# MCU.net
KiCad netlist of a schematic drawn in Altium Designer
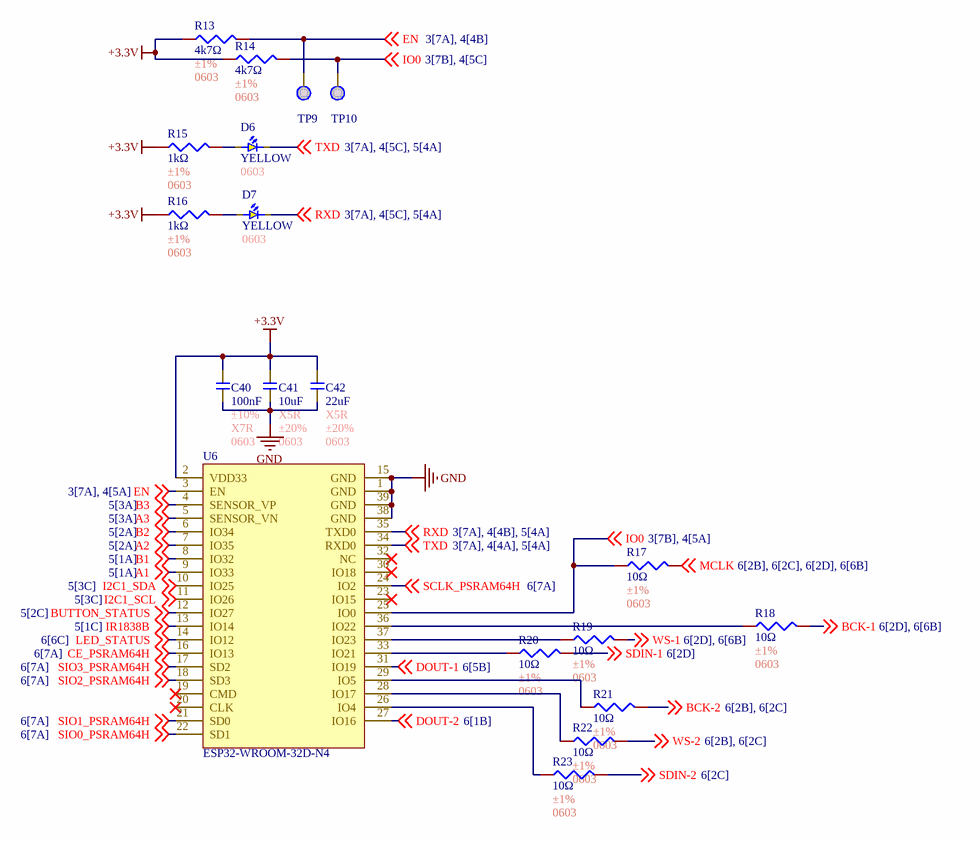
[diagram p0: MCU.SchDoc]

(export (version "E")
  (design (tool "Eeschema 10.0.6"))
  (components
    (comp (ref "C40")
      (value "100nF")
      (footprint "C0603")
      (description "50V 100nF X7R ±10% 0603 Multilayer Ceramic Capacitors MLCC - SMD/SMT ROHS")
      (fields
        (field (name "MANUFACTURER") "YAGEO")
        (field (name "MFR. PART #") "CC0603KRX7R9BB104")
        (field (name "TOLERANCE") "±10%")
        (field (name "TEMPERATURE COEFFICIENT") "X7R")
        (field (name "PACKAGE") "0603")
      )
      (libsource (lib "DSP_VERSION_1.0") (part "C0603_100nF_±10%_X7R"))
    )
    (comp (ref "C41")
      (value "10uF")
      (footprint "C0603")
      (description "25V 10uF X5R ±20% 0603 Multilayer Ceramic Capacitors MLCC - SMD/SMT ROHS")
      (fields
        (field (name "MANUFACTURER") "YAGEO")
        (field (name "MFR. PART #") "CC0603MRX5R8BB106")
        (field (name "TEMPERATURE COEFFICIENT") "X5R")
        (field (name "TOLERANCE") "±20%")
        (field (name "PACKAGE") "0603")
      )
      (libsource (lib "DSP_VERSION_1.0") (part "C0603_10uF_±10%_X7R"))
    )
    (comp (ref "C42")
      (value "22uF")
      (footprint "C0603")
      (description "6.3V 22uF X5R ±20% 0603 Multilayer Ceramic Capacitors MLCC - SMD/SMT ROHS")
      (fields
        (field (name "MANUFACTURER") "YAGEO")
        (field (name "MFR. PART #") "CC0603MRX5R5BB226")
        (field (name "TEMPERATURE COEFFICIENT") "X5R")
        (field (name "TOLERANCE") "±20%")
        (field (name "PACKAGE") "0603")
      )
      (libsource (lib "DSP_VERSION_1.0") (part "C0603_22uF_±20%_X5R"))
    )
    (comp (ref "D6")
      (value "YELLOW")
      (footprint "LED0603")
      (description "25mcd~40mcd Water Clear -40℃~+85℃ 624nm Red 120° 60mW 0402 LED Indication - Discrete ROHS")
      (fields
        (field (name "MANUFACTURER") "XINGLIGHT")
        (field (name "MFR. PART #") "XL-1005UGC")
        (field (name "PACKAGE") "0603")
      )
      (libsource (lib "LED") (part "D0603_YELLOW"))
    )
    (comp (ref "D7")
      (value "YELLOW")
      (footprint "LED0603")
      (description "25mcd~40mcd Water Clear -40℃~+85℃ 624nm Red 120° 60mW 0402 LED Indication - Discrete ROHS")
      (fields
        (field (name "MANUFACTURER") "XINGLIGHT")
        (field (name "MFR. PART #") "XL-1005UGC")
        (field (name "PACKAGE") "0603")
      )
      (libsource (lib "LED") (part "D0603_YELLOW"))
    )
    (comp (ref "R13")
      (value "4k7Ω")
      (footprint "R0603")
      (description "62.5mW Thick Film Resistor 50V ±1% ±200ppm/℃ 10Ω 0402 Chip Resistor - Surface Mount ROHS")
      (fields
        (field (name "MANUFACTURER") "YAGEO")
        (field (name "MFR. PART #") "RC0402FR-0710RL")
        (field (name "TOLERANCE") "±1%")
        (field (name "PACKAGE") "0603")
      )
      (libsource (lib "Resistor") (part "R0603_4k7Ω_±1%"))
    )
    (comp (ref "R14")
      (value "4k7Ω")
      (footprint "R0603")
      (description "62.5mW Thick Film Resistor 50V ±1% ±200ppm/℃ 10Ω 0402 Chip Resistor - Surface Mount ROHS")
      (fields
        (field (name "MANUFACTURER") "YAGEO")
        (field (name "MFR. PART #") "RC0402FR-0710RL")
        (field (name "TOLERANCE") "±1%")
        (field (name "PACKAGE") "0603")
      )
      (libsource (lib "Resistor") (part "R0603_4k7Ω_±1%"))
    )
    (comp (ref "R15")
      (value "1kΩ")
      (footprint "R0603")
      (description "62.5mW Thick Film Resistor 50V ±1% ±200ppm/℃ 10Ω 0402 Chip Resistor - Surface Mount ROHS")
      (fields
        (field (name "MANUFACTURER") "YAGEO")
        (field (name "MFR. PART #") "RC0402FR-0710RL")
        (field (name "TOLERANCE") "±1%")
        (field (name "PACKAGE") "0603")
      )
      (libsource (lib "Resistor") (part "R0603_1kΩ_±1%"))
    )
    (comp (ref "R16")
      (value "1kΩ")
      (footprint "R0603")
      (description "62.5mW Thick Film Resistor 50V ±1% ±200ppm/℃ 10Ω 0402 Chip Resistor - Surface Mount ROHS")
      (fields
        (field (name "MANUFACTURER") "YAGEO")
        (field (name "MFR. PART #") "RC0402FR-0710RL")
        (field (name "TOLERANCE") "±1%")
        (field (name "PACKAGE") "0603")
      )
      (libsource (lib "Resistor") (part "R0603_1kΩ_±1%"))
    )
    (comp (ref "R17")
      (value "10Ω")
      (footprint "R0603")
      (description "62.5mW Thick Film Resistor 50V ±1% ±200ppm/℃ 10Ω 0402 Chip Resistor - Surface Mount ROHS")
      (fields
        (field (name "MANUFACTURER") "YAGEO")
        (field (name "MFR. PART #") "RC0402FR-0710RL")
        (field (name "TOLERANCE") "±1%")
        (field (name "PACKAGE") "0603")
      )
      (libsource (lib "Resistor") (part "R0603_10Ω_±1%"))
    )
    (comp (ref "R18")
      (value "10Ω")
      (footprint "R0603")
      (description "62.5mW Thick Film Resistor 50V ±1% ±200ppm/℃ 10Ω 0402 Chip Resistor - Surface Mount ROHS")
      (fields
        (field (name "MANUFACTURER") "YAGEO")
        (field (name "MFR. PART #") "RC0402FR-0710RL")
        (field (name "TOLERANCE") "±1%")
        (field (name "PACKAGE") "0603")
      )
      (libsource (lib "Resistor") (part "R0603_10Ω_±1%"))
    )
    (comp (ref "R19")
      (value "10Ω")
      (footprint "R0603")
      (description "62.5mW Thick Film Resistor 50V ±1% ±200ppm/℃ 10Ω 0402 Chip Resistor - Surface Mount ROHS")
      (fields
        (field (name "MANUFACTURER") "YAGEO")
        (field (name "MFR. PART #") "RC0402FR-0710RL")
        (field (name "TOLERANCE") "±1%")
        (field (name "PACKAGE") "0603")
      )
      (libsource (lib "Resistor") (part "R0603_10Ω_±1%"))
    )
    (comp (ref "R20")
      (value "10Ω")
      (footprint "R0603")
      (description "62.5mW Thick Film Resistor 50V ±1% ±200ppm/℃ 10Ω 0402 Chip Resistor - Surface Mount ROHS")
      (fields
        (field (name "MANUFACTURER") "YAGEO")
        (field (name "MFR. PART #") "RC0402FR-0710RL")
        (field (name "TOLERANCE") "±1%")
        (field (name "PACKAGE") "0603")
      )
      (libsource (lib "Resistor") (part "R0603_10Ω_±1%"))
    )
    (comp (ref "R21")
      (value "10Ω")
      (footprint "R0603")
      (description "62.5mW Thick Film Resistor 50V ±1% ±200ppm/℃ 10Ω 0402 Chip Resistor - Surface Mount ROHS")
      (fields
        (field (name "MANUFACTURER") "YAGEO")
        (field (name "MFR. PART #") "RC0402FR-0710RL")
        (field (name "TOLERANCE") "±1%")
        (field (name "PACKAGE") "0603")
      )
      (libsource (lib "Resistor") (part "R0603_10Ω_±1%"))
    )
    (comp (ref "R22")
      (value "10Ω")
      (footprint "R0603")
      (description "62.5mW Thick Film Resistor 50V ±1% ±200ppm/℃ 10Ω 0402 Chip Resistor - Surface Mount ROHS")
      (fields
        (field (name "MANUFACTURER") "YAGEO")
        (field (name "MFR. PART #") "RC0402FR-0710RL")
        (field (name "TOLERANCE") "±1%")
        (field (name "PACKAGE") "0603")
      )
      (libsource (lib "Resistor") (part "R0603_10Ω_±1%"))
    )
    (comp (ref "R23")
      (value "10Ω")
      (footprint "R0603")
      (description "62.5mW Thick Film Resistor 50V ±1% ±200ppm/℃ 10Ω 0402 Chip Resistor - Surface Mount ROHS")
      (fields
        (field (name "MANUFACTURER") "YAGEO")
        (field (name "MFR. PART #") "RC0402FR-0710RL")
        (field (name "TOLERANCE") "±1%")
        (field (name "PACKAGE") "0603")
      )
      (libsource (lib "Resistor") (part "R0603_10Ω_±1%"))
    )
    (comp (ref "TP9") (value "TP") (footprint "TP") (libsource (lib "Other") (part "TP")))
    (comp (ref "TP10") (value "TP") (footprint "TP") (libsource (lib "Other") (part "TP")))
    (comp (ref "U6")
      (value "ESP32-WROOM-32D-N4")
      (footprint "ESP32-WROOM-32D-N4")
      (description "SMD,18x25.5mm WiFi Modules ROHS")
      (fields (field (name "MANUFACTURER") "ESPRESSIF") (field (name "LCSC PART #") "C473012"))
      (libsource (lib "MCU") (part "ESPRESSIF ESP32-WROOM-32D-N4"))
    )
  )
  (nets
    (net (code "1") (name "+3.3V") (class "Default")
      (node (ref "C40") (pin "2") (pinfunction "2_2") (pintype "passive"))
      (node (ref "C41") (pin "2") (pinfunction "2_2") (pintype "passive"))
      (node (ref "C42") (pin "2") (pinfunction "2_2") (pintype "passive"))
      (node (ref "R13") (pin "1") (pinfunction "1_1") (pintype "passive"))
      (node (ref "R14") (pin "1") (pinfunction "1_1") (pintype "passive"))
      (node (ref "R15") (pin "1") (pinfunction "1_1") (pintype "passive"))
      (node (ref "R16") (pin "1") (pinfunction "1_1") (pintype "passive"))
      (node (ref "U6") (pin "2") (pinfunction "VDD33_2") (pintype "passive"))
    )
    (net (code "2") (name "A1") (class "Default")
      (node (ref "U6") (pin "9") (pinfunction "IO33_9") (pintype "passive"))
    )
    (net (code "3") (name "A2") (class "Default")
      (node (ref "U6") (pin "7") (pinfunction "IO35_7") (pintype "passive"))
    )
    (net (code "4") (name "A3") (class "Default")
      (node (ref "U6") (pin "5") (pinfunction "SENSOR_VN_5") (pintype "passive"))
    )
    (net (code "5") (name "B1") (class "Default")
      (node (ref "U6") (pin "8") (pinfunction "IO32_8") (pintype "passive"))
    )
    (net (code "6") (name "B2") (class "Default")
      (node (ref "U6") (pin "6") (pinfunction "IO34_6") (pintype "passive"))
    )
    (net (code "7") (name "B3") (class "Default")
      (node (ref "U6") (pin "4") (pinfunction "SENSOR_VP_4") (pintype "passive"))
    )
    (net (code "8") (name "BCK-1") (class "Default")
      (node (ref "R18") (pin "2") (pinfunction "2_2") (pintype "passive"))
    )
    (net (code "9") (name "BCK-2") (class "Default")
      (node (ref "R21") (pin "2") (pinfunction "2_2") (pintype "passive"))
    )
    (net (code "10") (name "BUTTON_STATUS") (class "Default")
      (node (ref "U6") (pin "12") (pinfunction "IO27_12") (pintype "passive"))
    )
    (net (code "11") (name "CE_PSRAM64H") (class "Default")
      (node (ref "U6") (pin "16") (pinfunction "IO13_16") (pintype "passive"))
    )
    (net (code "12") (name "DOUT-1") (class "Default")
      (node (ref "U6") (pin "31") (pinfunction "IO19_31") (pintype "passive"))
    )
    (net (code "13") (name "DOUT-2") (class "Default")
      (node (ref "U6") (pin "27") (pinfunction "IO16_27") (pintype "passive"))
    )
    (net (code "14") (name "EN") (class "Default")
      (node (ref "R13") (pin "2") (pinfunction "2_2") (pintype "passive"))
      (node (ref "TP9") (pin "1") (pinfunction "1_1") (pintype "passive"))
      (node (ref "U6") (pin "3") (pinfunction "EN_3") (pintype "passive"))
    )
    (net (code "15") (name "GND") (class "Default")
      (node (ref "C40") (pin "1") (pinfunction "1_1") (pintype "passive"))
      (node (ref "C41") (pin "1") (pinfunction "1_1") (pintype "passive"))
      (node (ref "C42") (pin "1") (pinfunction "1_1") (pintype "passive"))
      (node (ref "U6") (pin "1") (pinfunction "GND_1") (pintype "passive"))
      (node (ref "U6") (pin "15") (pinfunction "GND_15") (pintype "passive"))
      (node (ref "U6") (pin "38") (pinfunction "GND_38") (pintype "passive"))
      (node (ref "U6") (pin "39") (pinfunction "GND_39") (pintype "passive"))
    )
    (net (code "16") (name "I2C1_SCL") (class "Default")
      (node (ref "U6") (pin "11") (pinfunction "IO26_11") (pintype "passive"))
    )
    (net (code "17") (name "I2C1_SDA") (class "Default")
      (node (ref "U6") (pin "10") (pinfunction "IO25_10") (pintype "passive"))
    )
    (net (code "18") (name "IO0") (class "Default")
      (node (ref "R14") (pin "2") (pinfunction "2_2") (pintype "passive"))
      (node (ref "R17") (pin "1") (pinfunction "1_1") (pintype "passive"))
      (node (ref "TP10") (pin "1") (pinfunction "1_1") (pintype "passive"))
      (node (ref "U6") (pin "25") (pinfunction "IO0_25") (pintype "passive"))
    )
    (net (code "19") (name "IR1838B") (class "Default")
      (node (ref "U6") (pin "13") (pinfunction "IO14_13") (pintype "passive"))
    )
    (net (code "20") (name "LED_STATUS") (class "Default")
      (node (ref "U6") (pin "14") (pinfunction "IO12_14") (pintype "passive"))
    )
    (net (code "21") (name "MCLK") (class "Default")
      (node (ref "R17") (pin "2") (pinfunction "2_2") (pintype "passive"))
    )
    (net (code "22") (name "Net-(D6-Pad2)") (class "Default")
      (node (ref "D6") (pin "2") (pinfunction "2_2") (pintype "passive"))
      (node (ref "R15") (pin "2") (pinfunction "2_2") (pintype "passive"))
    )
    (net (code "23") (name "Net-(D7-Pad2)") (class "Default")
      (node (ref "D7") (pin "2") (pinfunction "2_2") (pintype "passive"))
      (node (ref "R16") (pin "2") (pinfunction "2_2") (pintype "passive"))
    )
    (net (code "24") (name "Net-(U6-IO4)") (class "Default")
      (node (ref "R23") (pin "1") (pinfunction "1_1") (pintype "passive"))
      (node (ref "U6") (pin "26") (pinfunction "IO4_26") (pintype "passive"))
    )
    (net (code "25") (name "Net-(U6-IO5)") (class "Default")
      (node (ref "R21") (pin "1") (pinfunction "1_1") (pintype "passive"))
      (node (ref "U6") (pin "29") (pinfunction "IO5_29") (pintype "passive"))
    )
    (net (code "26") (name "Net-(U6-IO17)") (class "Default")
      (node (ref "R22") (pin "1") (pinfunction "1_1") (pintype "passive"))
      (node (ref "U6") (pin "28") (pinfunction "IO17_28") (pintype "passive"))
    )
    (net (code "27") (name "Net-(U6-IO21)") (class "Default")
      (node (ref "R20") (pin "1") (pinfunction "1_1") (pintype "passive"))
      (node (ref "U6") (pin "33") (pinfunction "IO21_33") (pintype "passive"))
    )
    (net (code "28") (name "Net-(U6-IO22)") (class "Default")
      (node (ref "R18") (pin "1") (pinfunction "1_1") (pintype "passive"))
      (node (ref "U6") (pin "36") (pinfunction "IO22_36") (pintype "passive"))
    )
    (net (code "29") (name "Net-(U6-IO23)") (class "Default")
      (node (ref "R19") (pin "1") (pinfunction "1_1") (pintype "passive"))
      (node (ref "U6") (pin "37") (pinfunction "IO23_37") (pintype "passive"))
    )
    (net (code "30") (name "RXD") (class "Default")
      (node (ref "D7") (pin "1") (pinfunction "1_1") (pintype "passive"))
      (node (ref "U6") (pin "35") (pinfunction "TXD0_35") (pintype "passive"))
    )
    (net (code "31") (name "SCLK_PSRAM64H") (class "Default")
      (node (ref "U6") (pin "24") (pinfunction "IO2_24") (pintype "passive"))
    )
    (net (code "32") (name "SDIN-1") (class "Default")
      (node (ref "R20") (pin "2") (pinfunction "2_2") (pintype "passive"))
    )
    (net (code "33") (name "SDIN-2") (class "Default")
      (node (ref "R23") (pin "2") (pinfunction "2_2") (pintype "passive"))
    )
    (net (code "34") (name "SIO0_PSRAM64H") (class "Default")
      (node (ref "U6") (pin "22") (pinfunction "SD1_22") (pintype "passive"))
    )
    (net (code "35") (name "SIO1_PSRAM64H") (class "Default")
      (node (ref "U6") (pin "21") (pinfunction "SD0_21") (pintype "passive"))
    )
    (net (code "36") (name "SIO2_PSRAM64H") (class "Default")
      (node (ref "U6") (pin "18") (pinfunction "SD3_18") (pintype "passive"))
    )
    (net (code "37") (name "SIO3_PSRAM64H") (class "Default")
      (node (ref "U6") (pin "17") (pinfunction "SD2_17") (pintype "passive"))
    )
    (net (code "38") (name "TXD") (class "Default")
      (node (ref "D6") (pin "1") (pinfunction "1_1") (pintype "passive"))
      (node (ref "U6") (pin "34") (pinfunction "RXD0_34") (pintype "passive"))
    )
    (net (code "39") (name "WS-1") (class "Default")
      (node (ref "R19") (pin "2") (pinfunction "2_2") (pintype "passive"))
    )
    (net (code "40") (name "WS-2") (class "Default")
      (node (ref "R22") (pin "2") (pinfunction "2_2") (pintype "passive"))
    )
    (net (code "41") (name "unconnected-(U6-CLK-Pad20)") (class "Default")
      (node (ref "U6") (pin "20") (pinfunction "CLK_20") (pintype "passive+no_connect"))
    )
    (net (code "42") (name "unconnected-(U6-CMD-Pad19)") (class "Default")
      (node (ref "U6") (pin "19") (pinfunction "CMD_19") (pintype "passive+no_connect"))
    )
    (net (code "43") (name "unconnected-(U6-IO15-Pad23)") (class "Default")
      (node (ref "U6") (pin "23") (pinfunction "IO15_23") (pintype "passive+no_connect"))
    )
    (net (code "44") (name "unconnected-(U6-IO18-Pad30)") (class "Default")
      (node (ref "U6") (pin "30") (pinfunction "IO18_30") (pintype "passive+no_connect"))
    )
    (net (code "45") (name "unconnected-(U6-NC-Pad32)") (class "Default")
      (node (ref "U6") (pin "32") (pinfunction "NC_32") (pintype "passive+no_connect"))
    )
  )
)
